# 09_USB.net
KiCad netlist of a schematic drawn in Altium Designer
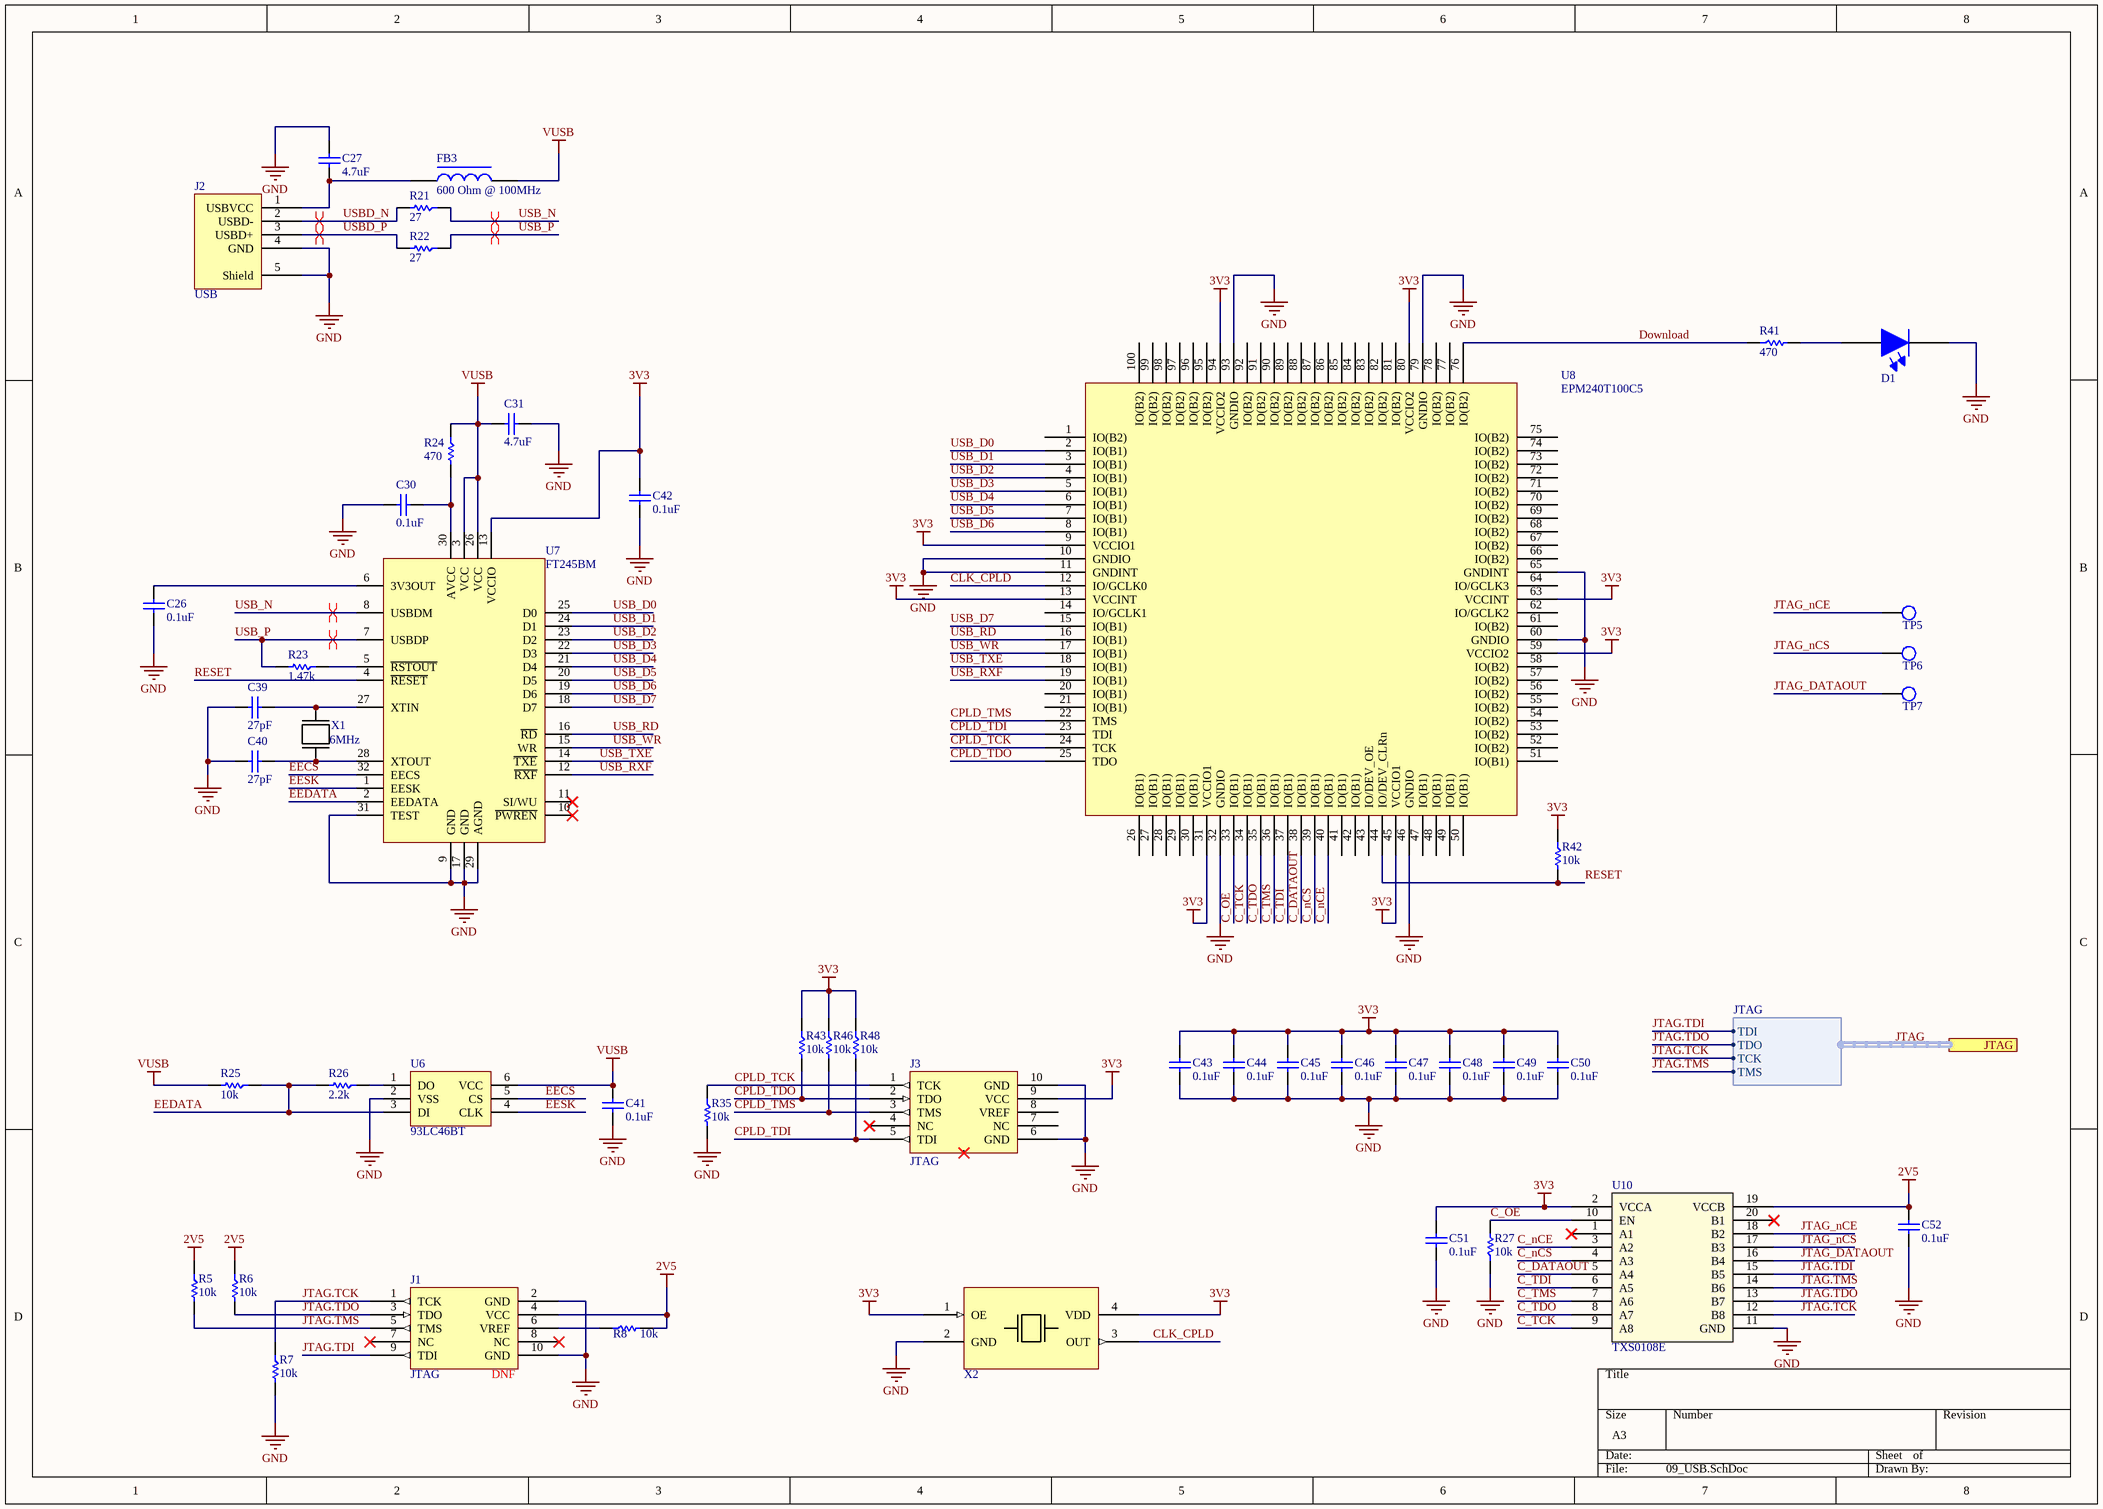
[diagram p0: 09_USB.SchDoc]

(export (version "E")
  (design (tool "Eeschema 10.0.6"))
  (components
    (comp (ref "C26")
      (value "0.1uF")
      (footprint "CAP0402R")
      (description "Capacitor")
      (libsource (lib "Quatro_SchLib") (part "C"))
    )
    (comp (ref "C27")
      (value "4.7uF")
      (footprint "CAP0805R")
      (description "Capacitor")
      (libsource (lib "Quatro_SchLib") (part "C"))
    )
    (comp (ref "C30")
      (value "0.1uF")
      (footprint "CAP0402R")
      (description "Capacitor")
      (libsource (lib "Quatro_SchLib") (part "C"))
    )
    (comp (ref "C31")
      (value "4.7uF")
      (footprint "CAP0805R")
      (description "Capacitor")
      (libsource (lib "Quatro_SchLib") (part "C"))
    )
    (comp (ref "C39")
      (value "27pF")
      (footprint "CAP0402R")
      (description "Capacitor")
      (libsource (lib "Quatro_SchLib") (part "C"))
    )
    (comp (ref "C40")
      (value "27pF")
      (footprint "CAP0402R")
      (description "Capacitor")
      (libsource (lib "Quatro_SchLib") (part "C"))
    )
    (comp (ref "C41")
      (value "0.1uF")
      (footprint "CAP0402R")
      (description "Capacitor")
      (libsource (lib "Quatro_SchLib") (part "C"))
    )
    (comp (ref "C42")
      (value "0.1uF")
      (footprint "CAP0402R")
      (description "Capacitor")
      (libsource (lib "Quatro_SchLib") (part "C"))
    )
    (comp (ref "C43")
      (value "0.1uF")
      (footprint "CAP0402R")
      (description "Capacitor")
      (libsource (lib "Quatro_SchLib") (part "C"))
    )
    (comp (ref "C44")
      (value "0.1uF")
      (footprint "CAP0402R")
      (description "Capacitor")
      (libsource (lib "Quatro_SchLib") (part "C"))
    )
    (comp (ref "C45")
      (value "0.1uF")
      (footprint "CAP0402R")
      (description "Capacitor")
      (libsource (lib "Quatro_SchLib") (part "C"))
    )
    (comp (ref "C46")
      (value "0.1uF")
      (footprint "CAP0402R")
      (description "Capacitor")
      (libsource (lib "Quatro_SchLib") (part "C"))
    )
    (comp (ref "C47")
      (value "0.1uF")
      (footprint "CAP0402R")
      (description "Capacitor")
      (libsource (lib "Quatro_SchLib") (part "C"))
    )
    (comp (ref "C48")
      (value "0.1uF")
      (footprint "CAP0402R")
      (description "Capacitor")
      (libsource (lib "Quatro_SchLib") (part "C"))
    )
    (comp (ref "C49")
      (value "0.1uF")
      (footprint "CAP0402R")
      (description "Capacitor")
      (libsource (lib "Quatro_SchLib") (part "C"))
    )
    (comp (ref "C50")
      (value "0.1uF")
      (footprint "CAP0402R")
      (description "Capacitor")
      (libsource (lib "Quatro_SchLib") (part "C"))
    )
    (comp (ref "C51")
      (value "0.1uF")
      (footprint "CAP0402R")
      (description "Capacitor")
      (libsource (lib "Quatro_SchLib") (part "C"))
    )
    (comp (ref "C52")
      (value "0.1uF")
      (footprint "CAP0402R")
      (description "Capacitor")
      (libsource (lib "Quatro_SchLib") (part "C"))
    )
    (comp (ref "D1")
      (value "LED")
      (footprint "0805D-RED")
      (description "Generic LED")
      (fields
        (field (name "01 CREATED BY") "Thomas Harper")
        (field (name "02 REVIEWED BY") "Rodrigo Maureira @ 2018-04-05")
        (field (name "PUBLISHER") "MUEEC")
      )
      (libsource (lib "Quatro_SchLib") (part "LED_SMD_Generic"))
    )
    (comp (ref "FB3")
      (value "600 Ohm @ 100MHz")
      (footprint "RES0805R")
      (description "Ferrite Bead")
      (libsource (lib "Quatro_SchLib") (part "Ferrite_Bead"))
    )
    (comp (ref "J1")
      (value "JTAG")
      (footprint "BOXEDVERT10")
      (description "JTAG connector")
      (fields (field (name "LOAD") "DNF"))
      (libsource (lib "Quatro_SchLib") (part "JTAG_CON"))
    )
    (comp (ref "J2")
      (value "USB")
      (footprint "USBPLUG")
      (description "USB B Type Connector")
      (libsource (lib "Quatro_SchLib") (part "USBPLUG"))
    )
    (comp (ref "J3")
      (value "JTAG")
      (footprint "TC2050-IDC-NL")
      (description "Contacts for TC2050-IDC-NL")
      (fields (field (name "01 CREATED BY") "Rodrigo Maureira") (field (name "PUBLISHER") "MUEEC"))
      (libsource (lib "Quatro_SchLib") (part "JTAG_CON_POGO"))
    )
    (comp (ref "R5")
      (value "10k")
      (footprint "RES0603R")
      (description "Resistor")
      (libsource (lib "Quatro_SchLib") (part "R"))
    )
    (comp (ref "R6")
      (value "10k")
      (footprint "RES0603R")
      (description "Resistor")
      (libsource (lib "Quatro_SchLib") (part "R"))
    )
    (comp (ref "R7")
      (value "10k")
      (footprint "RES0603R")
      (description "Resistor")
      (libsource (lib "Quatro_SchLib") (part "R"))
    )
    (comp (ref "R8")
      (value "10k")
      (footprint "RES0603R")
      (description "Resistor")
      (libsource (lib "Quatro_SchLib") (part "R"))
    )
    (comp (ref "R21")
      (value "27")
      (footprint "RES0402R")
      (description "Resistor")
      (libsource (lib "Quatro_SchLib") (part "R"))
    )
    (comp (ref "R22")
      (value "27")
      (footprint "RES0402R")
      (description "Resistor")
      (libsource (lib "Quatro_SchLib") (part "R"))
    )
    (comp (ref "R23")
      (value "1.47k")
      (footprint "RES0402R")
      (description "Resistor")
      (libsource (lib "Quatro_SchLib") (part "R"))
    )
    (comp (ref "R24")
      (value "470")
      (footprint "RES0402R")
      (description "Resistor")
      (libsource (lib "Quatro_SchLib") (part "R"))
    )
    (comp (ref "R25")
      (value "10k")
      (footprint "RES0603R")
      (description "Resistor")
      (libsource (lib "Quatro_SchLib") (part "R"))
    )
    (comp (ref "R26")
      (value "2.2k")
      (footprint "RES0603R")
      (description "Resistor")
      (libsource (lib "Quatro_SchLib") (part "R"))
    )
    (comp (ref "R27")
      (value "10k")
      (footprint "RES0603R")
      (description "Resistor")
      (libsource (lib "Quatro_SchLib") (part "R"))
    )
    (comp (ref "R35")
      (value "10k")
      (footprint "RES0603R")
      (description "Resistor")
      (libsource (lib "Quatro_SchLib") (part "R"))
    )
    (comp (ref "R41")
      (value "470")
      (footprint "RES0402R")
      (description "Resistor")
      (libsource (lib "Quatro_SchLib") (part "R"))
    )
    (comp (ref "R42")
      (value "10k")
      (footprint "RES0603R")
      (description "Resistor")
      (libsource (lib "Quatro_SchLib") (part "R"))
    )
    (comp (ref "R43")
      (value "10k")
      (footprint "RES0603R")
      (description "Resistor")
      (libsource (lib "Quatro_SchLib") (part "R"))
    )
    (comp (ref "R46")
      (value "10k")
      (footprint "RES0603R")
      (description "Resistor")
      (libsource (lib "Quatro_SchLib") (part "R"))
    )
    (comp (ref "R48")
      (value "10k")
      (footprint "RES0603R")
      (description "Resistor")
      (libsource (lib "Quatro_SchLib") (part "R"))
    )
    (comp (ref "TP5")
      (value "TestPoint")
      (footprint "TestPoint")
      (description "Test Point")
      (libsource (lib "Quatro_SchLib") (part "TestPoint"))
    )
    (comp (ref "TP6")
      (value "TestPoint")
      (footprint "TestPoint")
      (description "Test Point")
      (libsource (lib "Quatro_SchLib") (part "TestPoint"))
    )
    (comp (ref "TP7")
      (value "TestPoint")
      (footprint "TestPoint")
      (description "Test Point")
      (libsource (lib "Quatro_SchLib") (part "TestPoint"))
    )
    (comp (ref "U6")
      (value "93LC46BT")
      (footprint "SOT23-6")
      (description "1024-Bit Serial CMOS EEPROM")
      (libsource (lib "Quatro_SchLib") (part "FM93C46"))
    )
    (comp (ref "U7")
      (value "FT245BM")
      (footprint "LQFP32")
      (description "USB FIFO IC")
      (libsource (lib "Quatro_SchLib") (part "FT245BM"))
    )
    (comp (ref "U8")
      (value "EPM240T100C5")
      (footprint "TQFP100-14mm")
      (libsource (lib "Quatro_SchLib") (part "EPM240T100C5"))
    )
    (comp (ref "U10")
      (value "TXS0108E")
      (footprint "TSSOP20-4.4mm")
      (description "8-BIT BIDIRECTIONAL VOLTAGE-LEVEL TRANSLATOR  FOR OPEN-DRAIN AND PUSH-PULL APPLICATIONS")
      (libsource (lib "Quatro_SchLib") (part "TXS0108E"))
    )
    (comp (ref "X1")
      (value "6MHz")
      (footprint "HC-49/US")
      (description "ECS-60-20-5PX-TR")
      (libsource (lib "Quatro_SchLib") (part "Crystal 6MHz"))
    )
    (comp (ref "X2")
      (value "24Mhz Oscillator")
      (footprint "CX32225SB")
      (fields (field (name "01 CREATED BY") "Rodrigo Maureira") (field (name "PUBLISHER") "MUEEC"))
      (libsource (lib "Quatro_SchLib") (part "24Mhz Oscillator"))
    )
  )
  (nets
    (net (code "2") (name "/CLK_CPLD") (class "Default")
      (node (ref "U8") (pin "12") (pinfunction "IO/GCLK0_12") (pintype "passive"))
      (node (ref "X2") (pin "3") (pinfunction "OUT_3") (pintype "output"))
    )
    (net (code "3") (name "/CPLD_TCK") (class "Default")
      (node (ref "J3") (pin "1") (pinfunction "TCK_1") (pintype "output"))
      (node (ref "R35") (pin "1") (pintype "passive"))
      (node (ref "U8") (pin "24") (pinfunction "TCK_24") (pintype "passive"))
    )
    (net (code "4") (name "/CPLD_TDI") (class "Default")
      (node (ref "J3") (pin "5") (pinfunction "TDI_5") (pintype "output"))
      (node (ref "R48") (pin "2") (pintype "passive"))
      (node (ref "U8") (pin "23") (pinfunction "TDI_23") (pintype "passive"))
    )
    (net (code "5") (name "/CPLD_TDO") (class "Default")
      (node (ref "J3") (pin "2") (pinfunction "TDO_2") (pintype "input"))
      (node (ref "R43") (pin "2") (pintype "passive"))
      (node (ref "U8") (pin "25") (pinfunction "TDO_25") (pintype "passive"))
    )
    (net (code "6") (name "/CPLD_TMS") (class "Default")
      (node (ref "J3") (pin "3") (pinfunction "TMS_3") (pintype "output"))
      (node (ref "R46") (pin "2") (pintype "passive"))
      (node (ref "U8") (pin "22") (pinfunction "TMS_22") (pintype "passive"))
    )
    (net (code "7") (name "/C_DATAOUT") (class "Default")
      (node (ref "U10") (pin "5") (pinfunction "A4_5") (pintype "passive"))
      (node (ref "U8") (pin "38") (pinfunction "IO(B1)_38") (pintype "passive"))
    )
    (net (code "8") (name "/C_OE") (class "Default")
      (node (ref "R27") (pin "2") (pintype "passive"))
      (node (ref "U10") (pin "10") (pinfunction "EN_10") (pintype "passive"))
      (node (ref "U8") (pin "33") (pinfunction "IO(B1)_33") (pintype "passive"))
    )
    (net (code "9") (name "/C_TCK") (class "Default")
      (node (ref "U10") (pin "9") (pinfunction "A8_9") (pintype "passive"))
      (node (ref "U8") (pin "34") (pinfunction "IO(B1)_34") (pintype "passive"))
    )
    (net (code "10") (name "/C_TDI") (class "Default")
      (node (ref "U10") (pin "6") (pinfunction "A5_6") (pintype "passive"))
      (node (ref "U8") (pin "37") (pinfunction "IO(B1)_37") (pintype "passive"))
    )
    (net (code "11") (name "/C_TDO") (class "Default")
      (node (ref "U10") (pin "8") (pinfunction "A7_8") (pintype "passive"))
      (node (ref "U8") (pin "35") (pinfunction "IO(B1)_35") (pintype "passive"))
    )
    (net (code "12") (name "/C_TMS") (class "Default")
      (node (ref "U10") (pin "7") (pinfunction "A6_7") (pintype "passive"))
      (node (ref "U8") (pin "36") (pinfunction "IO(B1)_36") (pintype "passive"))
    )
    (net (code "13") (name "/C_nCE") (class "Default")
      (node (ref "U10") (pin "3") (pinfunction "A2_3") (pintype "passive"))
      (node (ref "U8") (pin "40") (pinfunction "IO(B1)_40") (pintype "passive"))
    )
    (net (code "14") (name "/C_nCS") (class "Default")
      (node (ref "U10") (pin "4") (pinfunction "A3_4") (pintype "passive"))
      (node (ref "U8") (pin "39") (pinfunction "IO(B1)_39") (pintype "passive"))
    )
    (net (code "15") (name "/Download") (class "Default")
      (node (ref "R41") (pin "1") (pintype "passive"))
      (node (ref "U8") (pin "76") (pinfunction "IO(B2)_76") (pintype "passive"))
    )
    (net (code "16") (name "/EECS") (class "Default")
      (node (ref "U6") (pin "5") (pinfunction "CS_5") (pintype "passive"))
      (node (ref "U7") (pin "32") (pinfunction "EECS_32") (pintype "passive"))
    )
    (net (code "17") (name "/EEDATA") (class "Default")
      (node (ref "R25") (pin "1") (pintype "passive"))
      (node (ref "R26") (pin "2") (pintype "passive"))
      (node (ref "U6") (pin "3") (pinfunction "DI_3") (pintype "passive"))
      (node (ref "U7") (pin "2") (pinfunction "EEDATA_2") (pintype "passive"))
    )
    (net (code "18") (name "/EESK") (class "Default")
      (node (ref "U6") (pin "4") (pinfunction "CLK_4") (pintype "passive"))
      (node (ref "U7") (pin "1") (pinfunction "EESK_1") (pintype "passive"))
    )
    (net (code "19") (name "/JTAG.TCK") (class "Default")
      (node (ref "J1") (pin "1") (pinfunction "TCK_1") (pintype "output"))
      (node (ref "R7") (pin "1") (pintype "passive"))
      (node (ref "U10") (pin "12") (pinfunction "B8_12") (pintype "passive"))
    )
    (net (code "20") (name "/JTAG.TDI") (class "Default")
      (node (ref "J1") (pin "9") (pinfunction "TDI_9") (pintype "output"))
      (node (ref "U10") (pin "15") (pinfunction "B5_15") (pintype "passive"))
    )
    (net (code "21") (name "/JTAG.TDO") (class "Default")
      (node (ref "J1") (pin "3") (pinfunction "TDO_3") (pintype "input"))
      (node (ref "R6") (pin "2") (pintype "passive"))
      (node (ref "U10") (pin "13") (pinfunction "B7_13") (pintype "passive"))
    )
    (net (code "22") (name "/JTAG.TMS") (class "Default")
      (node (ref "J1") (pin "5") (pinfunction "TMS_5") (pintype "output"))
      (node (ref "R5") (pin "2") (pintype "passive"))
      (node (ref "U10") (pin "14") (pinfunction "B6_14") (pintype "passive"))
    )
    (net (code "23") (name "/JTAG_DATAOUT") (class "Default")
      (node (ref "TP7") (pin "0") (pinfunction "TP_0") (pintype "passive"))
      (node (ref "U10") (pin "16") (pinfunction "B4_16") (pintype "passive"))
    )
    (net (code "24") (name "/JTAG_nCE") (class "Default")
      (node (ref "TP5") (pin "0") (pinfunction "TP_0") (pintype "passive"))
      (node (ref "U10") (pin "18") (pinfunction "B2_18") (pintype "passive"))
    )
    (net (code "25") (name "/JTAG_nCS") (class "Default")
      (node (ref "TP6") (pin "0") (pinfunction "TP_0") (pintype "passive"))
      (node (ref "U10") (pin "17") (pinfunction "B3_17") (pintype "passive"))
    )
    (net (code "27") (name "/RESET") (class "Default")
      (node (ref "R42") (pin "2") (pintype "passive"))
      (node (ref "U7") (pin "4") (pinfunction "~{RESET}_4") (pintype "passive"))
      (node (ref "U8") (pin "44") (pinfunction "IO/DEV_CLRn_44") (pintype "passive"))
    )
    (net (code "28") (name "/USBD_N") (class "Default")
      (node (ref "J2") (pin "2") (pinfunction "USBD-_2") (pintype "passive"))
      (node (ref "R21") (pin "2") (pintype "passive"))
    )
    (net (code "29") (name "/USBD_P") (class "Default")
      (node (ref "J2") (pin "3") (pinfunction "USBD+_3") (pintype "passive"))
      (node (ref "R22") (pin "2") (pintype "passive"))
    )
    (net (code "30") (name "/USB_D0") (class "Default")
      (node (ref "U7") (pin "25") (pinfunction "D0_25") (pintype "passive"))
      (node (ref "U8") (pin "2") (pinfunction "IO(B1)_2") (pintype "passive"))
    )
    (net (code "31") (name "/USB_D1") (class "Default")
      (node (ref "U7") (pin "24") (pinfunction "D1_24") (pintype "passive"))
      (node (ref "U8") (pin "3") (pinfunction "IO(B1)_3") (pintype "passive"))
    )
    (net (code "32") (name "/USB_D2") (class "Default")
      (node (ref "U7") (pin "23") (pinfunction "D2_23") (pintype "passive"))
      (node (ref "U8") (pin "4") (pinfunction "IO(B1)_4") (pintype "passive"))
    )
    (net (code "33") (name "/USB_D3") (class "Default")
      (node (ref "U7") (pin "22") (pinfunction "D3_22") (pintype "passive"))
      (node (ref "U8") (pin "5") (pinfunction "IO(B1)_5") (pintype "passive"))
    )
    (net (code "34") (name "/USB_D4") (class "Default")
      (node (ref "U7") (pin "21") (pinfunction "D4_21") (pintype "passive"))
      (node (ref "U8") (pin "6") (pinfunction "IO(B1)_6") (pintype "passive"))
    )
    (net (code "35") (name "/USB_D5") (class "Default")
      (node (ref "U7") (pin "20") (pinfunction "D5_20") (pintype "passive"))
      (node (ref "U8") (pin "7") (pinfunction "IO(B1)_7") (pintype "passive"))
    )
    (net (code "36") (name "/USB_D6") (class "Default")
      (node (ref "U7") (pin "19") (pinfunction "D6_19") (pintype "passive"))
      (node (ref "U8") (pin "8") (pinfunction "IO(B1)_8") (pintype "passive"))
    )
    (net (code "37") (name "/USB_D7") (class "Default")
      (node (ref "U7") (pin "18") (pinfunction "D7_18") (pintype "passive"))
      (node (ref "U8") (pin "15") (pinfunction "IO(B1)_15") (pintype "passive"))
    )
    (net (code "38") (name "/USB_N") (class "Default")
      (node (ref "R21") (pin "1") (pintype "passive"))
      (node (ref "U7") (pin "8") (pinfunction "USBDM_8") (pintype "passive"))
    )
    (net (code "39") (name "/USB_P") (class "Default")
      (node (ref "R22") (pin "1") (pintype "passive"))
      (node (ref "R23") (pin "2") (pintype "passive"))
      (node (ref "U7") (pin "7") (pinfunction "USBDP_7") (pintype "passive"))
    )
    (net (code "40") (name "/USB_RD") (class "Default")
      (node (ref "U7") (pin "16") (pinfunction "~{RD}_16") (pintype "passive"))
      (node (ref "U8") (pin "16") (pinfunction "IO(B1)_16") (pintype "passive"))
    )
    (net (code "41") (name "/USB_RXF") (class "Default")
      (node (ref "U7") (pin "12") (pinfunction "~{RXF}_12") (pintype "passive"))
      (node (ref "U8") (pin "19") (pinfunction "IO(B1)_19") (pintype "passive"))
    )
    (net (code "42") (name "/USB_TXE") (class "Default")
      (node (ref "U7") (pin "14") (pinfunction "~{TXE}_14") (pintype "passive"))
      (node (ref "U8") (pin "18") (pinfunction "IO(B1)_18") (pintype "passive"))
    )
    (net (code "43") (name "/USB_WR") (class "Default")
      (node (ref "U7") (pin "15") (pinfunction "WR_15") (pintype "passive"))
      (node (ref "U8") (pin "17") (pinfunction "IO(B1)_17") (pintype "passive"))
    )
    (net (code "44") (name "2V5") (class "Default")
      (node (ref "C52") (pin "1") (pinfunction "1_1") (pintype "passive"))
      (node (ref "J1") (pin "4") (pinfunction "VCC_4") (pintype "power_in"))
      (node (ref "R5") (pin "1") (pintype "passive"))
      (node (ref "R6") (pin "1") (pintype "passive"))
      (node (ref "R8") (pin "2") (pintype "passive"))
      (node (ref "U10") (pin "19") (pinfunction "VCCB_19") (pintype "passive"))
    )
    (net (code "45") (name "3V3") (class "Default")
      (node (ref "C42") (pin "2") (pinfunction "2_2") (pintype "passive"))
      (node (ref "C43") (pin "1") (pinfunction "1_1") (pintype "passive"))
      (node (ref "C44") (pin "1") (pinfunction "1_1") (pintype "passive"))
      (node (ref "C45") (pin "1") (pinfunction "1_1") (pintype "passive"))
      (node (ref "C46") (pin "1") (pinfunction "1_1") (pintype "passive"))
      (node (ref "C47") (pin "1") (pinfunction "1_1") (pintype "passive"))
      (node (ref "C48") (pin "1") (pinfunction "1_1") (pintype "passive"))
      (node (ref "C49") (pin "1") (pinfunction "1_1") (pintype "passive"))
      (node (ref "C50") (pin "1") (pinfunction "1_1") (pintype "passive"))
      (node (ref "C51") (pin "1") (pinfunction "1_1") (pintype "passive"))
      (node (ref "J3") (pin "9") (pinfunction "VCC_9") (pintype "power_in"))
      (node (ref "R42") (pin "1") (pintype "passive"))
      (node (ref "R43") (pin "1") (pintype "passive"))
      (node (ref "R46") (pin "1") (pintype "passive"))
      (node (ref "R48") (pin "1") (pintype "passive"))
      (node (ref "U10") (pin "2") (pinfunction "VCCA_2") (pintype "passive"))
      (node (ref "U7") (pin "13") (pinfunction "VCCIO_13") (pintype "passive"))
      (node (ref "U8") (pin "13") (pinfunction "VCCINT_13") (pintype "passive"))
      (node (ref "U8") (pin "31") (pinfunction "VCCIO1_31") (pintype "passive"))
      (node (ref "U8") (pin "45") (pinfunction "VCCIO1_45") (pintype "passive"))
      (node (ref "U8") (pin "59") (pinfunction "VCCIO2_59") (pintype "passive"))
      (node (ref "U8") (pin "63") (pinfunction "VCCINT_63") (pintype "passive"))
      (node (ref "U8") (pin "80") (pinfunction "VCCIO2_80") (pintype "passive"))
      (node (ref "U8") (pin "9") (pinfunction "VCCIO1_9") (pintype "passive"))
      (node (ref "U8") (pin "94") (pinfunction "VCCIO2_94") (pintype "passive"))
      (node (ref "X2") (pin "1") (pinfunction "OE_1") (pintype "input"))
      (node (ref "X2") (pin "4") (pinfunction "VDD_4") (pintype "power_in"))
    )
    (net (code "46") (name "GND") (class "Default")
      (node (ref "C26") (pin "2") (pinfunction "2_2") (pintype "passive"))
      (node (ref "C27") (pin "1") (pinfunction "1_1") (pintype "passive"))
      (node (ref "C30") (pin "1") (pinfunction "1_1") (pintype "passive"))
      (node (ref "C31") (pin "2") (pinfunction "2_2") (pintype "passive"))
      (node (ref "C39") (pin "1") (pinfunction "1_1") (pintype "passive"))
      (node (ref "C40") (pin "1") (pinfunction "1_1") (pintype "passive"))
      (node (ref "C41") (pin "1") (pinfunction "1_1") (pintype "passive"))
      (node (ref "C42") (pin "1") (pinfunction "1_1") (pintype "passive"))
      (node (ref "C43") (pin "2") (pinfunction "2_2") (pintype "passive"))
      (node (ref "C44") (pin "2") (pinfunction "2_2") (pintype "passive"))
      (node (ref "C45") (pin "2") (pinfunction "2_2") (pintype "passive"))
      (node (ref "C46") (pin "2") (pinfunction "2_2") (pintype "passive"))
      (node (ref "C47") (pin "2") (pinfunction "2_2") (pintype "passive"))
      (node (ref "C48") (pin "2") (pinfunction "2_2") (pintype "passive"))
      (node (ref "C49") (pin "2") (pinfunction "2_2") (pintype "passive"))
      (node (ref "C50") (pin "2") (pinfunction "2_2") (pintype "passive"))
      (node (ref "C51") (pin "2") (pinfunction "2_2") (pintype "passive"))
      (node (ref "C52") (pin "2") (pinfunction "2_2") (pintype "passive"))
      (node (ref "D1") (pin "K") (pinfunction "CATHODE_K") (pintype "passive"))
      (node (ref "J1") (pin "10") (pinfunction "GND_10") (pintype "passive"))
      (node (ref "J1") (pin "2") (pinfunction "GND_2") (pintype "passive"))
      (node (ref "J2") (pin "4") (pinfunction "GND_4") (pintype "passive"))
      (node (ref "J2") (pin "5") (pinfunction "Shield_5") (pintype "passive"))
      (node (ref "J3") (pin "10") (pinfunction "GND_10") (pintype "passive"))
      (node (ref "J3") (pin "6") (pinfunction "GND_6") (pintype "passive"))
      (node (ref "R27") (pin "1") (pintype "passive"))
      (node (ref "R35") (pin "2") (pintype "passive"))
      (node (ref "R7") (pin "2") (pintype "passive"))
      (node (ref "U10") (pin "11") (pinfunction "GND_11") (pintype "passive"))
      (node (ref "U6") (pin "2") (pinfunction "VSS_2") (pintype "passive"))
      (node (ref "U7") (pin "17") (pinfunction "GND_17") (pintype "passive"))
      (node (ref "U7") (pin "29") (pinfunction "AGND_29") (pintype "passive"))
      (node (ref "U7") (pin "31") (pinfunction "TEST_31") (pintype "passive"))
      (node (ref "U7") (pin "9") (pinfunction "GND_9") (pintype "passive"))
      (node (ref "U8") (pin "10") (pinfunction "GNDIO_10") (pintype "passive"))
      (node (ref "U8") (pin "11") (pinfunction "GNDINT_11") (pintype "passive"))
      (node (ref "U8") (pin "32") (pinfunction "GNDIO_32") (pintype "passive"))
      (node (ref "U8") (pin "46") (pinfunction "GNDIO_46") (pintype "passive"))
      (node (ref "U8") (pin "60") (pinfunction "GNDIO_60") (pintype "passive"))
      (node (ref "U8") (pin "65") (pinfunction "GNDINT_65") (pintype "passive"))
      (node (ref "U8") (pin "79") (pinfunction "GNDIO_79") (pintype "passive"))
      (node (ref "U8") (pin "93") (pinfunction "GNDIO_93") (pintype "passive"))
      (node (ref "X2") (pin "2") (pinfunction "GND_2") (pintype "power_in"))
    )
    (net (code "47") (name "Net-(D1-ANODE)") (class "Default")
      (node (ref "D1") (pin "A") (pinfunction "ANODE_A") (pintype "passive"))
      (node (ref "R41") (pin "2") (pintype "passive"))
    )
    (net (code "48") (name "Net-(J1-VREF)") (class "Default")
      (node (ref "J1") (pin "6") (pinfunction "VREF_6") (pintype "passive"))
      (node (ref "R8") (pin "1") (pintype "passive"))
    )
    (net (code "49") (name "Net-(J2-USBVCC)") (class "Default")
      (node (ref "C27") (pin "2") (pinfunction "2_2") (pintype "passive"))
      (node (ref "FB3") (pin "1") (pinfunction "1_1") (pintype "passive"))
      (node (ref "J2") (pin "1") (pinfunction "USBVCC_1") (pintype "passive"))
    )
    (net (code "50") (name "Net-(U6-DO)") (class "Default")
      (node (ref "R26") (pin "1") (pintype "passive"))
      (node (ref "U6") (pin "1") (pinfunction "DO_1") (pintype "passive"))
    )
    (net (code "51") (name "Net-(U7-3V3OUT)") (class "Default")
      (node (ref "C26") (pin "1") (pinfunction "1_1") (pintype "passive"))
      (node (ref "U7") (pin "6") (pinfunction "3V3OUT_6") (pintype "passive"))
    )
    (net (code "52") (name "Net-(U7-AVCC)") (class "Default")
      (node (ref "C30") (pin "2") (pinfunction "2_2") (pintype "passive"))
      (node (ref "R24") (pin "2") (pintype "passive"))
      (node (ref "U7") (pin "30") (pinfunction "AVCC_30") (pintype "passive"))
    )
    (net (code "53") (name "Net-(U7-XTIN)") (class "Default")
      (node (ref "C39") (pin "2") (pinfunction "2_2") (pintype "passive"))
      (node (ref "U7") (pin "27") (pinfunction "XTIN_27") (pintype "passive"))
      (node (ref "X1") (pin "1") (pinfunction "1_1") (pintype "passive"))
    )
    (net (code "54") (name "Net-(U7-XTOUT)") (class "Default")
      (node (ref "C40") (pin "2") (pinfunction "2_2") (pintype "passive"))
      (node (ref "U7") (pin "28") (pinfunction "XTOUT_28") (pintype "passive"))
      (node (ref "X1") (pin "2") (pinfunction "2_2") (pintype "passive"))
    )
    (net (code "55") (name "Net-(U7-~{RSTOUT})") (class "Default")
      (node (ref "R23") (pin "1") (pintype "passive"))
      (node (ref "U7") (pin "5") (pinfunction "~{RSTOUT}_5") (pintype "passive"))
    )
    (net (code "56") (name "VUSB") (class "Default")
      (node (ref "C31") (pin "1") (pinfunction "1_1") (pintype "passive"))
      (node (ref "C41") (pin "2") (pinfunction "2_2") (pintype "passive"))
      (node (ref "FB3") (pin "2") (pinfunction "2_2") (pintype "passive"))
      (node (ref "R24") (pin "1") (pintype "passive"))
      (node (ref "R25") (pin "2") (pintype "passive"))
      (node (ref "U6") (pin "6") (pinfunction "VCC_6") (pintype "passive"))
      (node (ref "U7") (pin "26") (pinfunction "VCC_26") (pintype "passive"))
      (node (ref "U7") (pin "3") (pinfunction "VCC_3") (pintype "passive"))
    )
    (net (code "57") (name "unconnected-(J1-NC-Pad7)") (class "Default")
      (node (ref "J1") (pin "7") (pinfunction "NC_7") (pintype "passive+no_connect"))
    )
    (net (code "58") (name "unconnected-(J1-NC-Pad8)") (class "Default")
      (node (ref "J1") (pin "8") (pinfunction "NC_8") (pintype "passive+no_connect"))
    )
    (net (code "59") (name "unconnected-(J3-NC-Pad4)") (class "Default")
      (node (ref "J3") (pin "4") (pinfunction "NC_4") (pintype "passive+no_connect"))
    )
    (net (code "60") (name "unconnected-(J3-NC-Pad7)") (class "Default")
      (node (ref "J3") (pin "7") (pinfunction "NC_7") (pintype "passive"))
    )
    (net (code "61") (name "unconnected-(J3-Pad0)") (class "Default")
      (node (ref "J3") (pin "0") (pinfunction "0_0") (pintype "passive+no_connect"))
    )
    (net (code "62") (name "unconnected-(J3-VREF-Pad8)") (class "Default")
      (node (ref "J3") (pin "8") (pinfunction "VREF_8") (pintype "passive"))
    )
    (net (code "63") (name "unconnected-(U7-SI{slash}WU-Pad11)") (class "Default")
      (node (ref "U7") (pin "11") (pinfunction "SI/WU_11") (pintype "passive+no_connect"))
    )
    (net (code "64") (name "unconnected-(U7-~{PWREN}-Pad10)") (class "Default")
      (node (ref "U7") (pin "10") (pinfunction "~{PWREN}_10") (pintype "passive+no_connect"))
    )
    (net (code "65") (name "unconnected-(U8-IO(B1)-Pad20)") (class "Default")
      (node (ref "U8") (pin "20") (pinfunction "IO(B1)_20") (pintype "passive"))
    )
    (net (code "66") (name "unconnected-(U8-IO(B1)-Pad21)") (class "Default")
      (node (ref "U8") (pin "21") (pinfunction "IO(B1)_21") (pintype "passive"))
    )
    (net (code "67") (name "unconnected-(U8-IO(B1)-Pad26)") (class "Default")
      (node (ref "U8") (pin "26") (pinfunction "IO(B1)_26") (pintype "passive"))
    )
    (net (code "68") (name "unconnected-(U8-IO(B1)-Pad27)") (class "Default")
      (node (ref "U8") (pin "27") (pinfunction "IO(B1)_27") (pintype "passive"))
    )
    (net (code "69") (name "unconnected-(U8-IO(B1)-Pad28)") (class "Default")
      (node (ref "U8") (pin "28") (pinfunction "IO(B1)_28") (pintype "passive"))
    )
    (net (code "70") (name "unconnected-(U8-IO(B1)-Pad29)") (class "Default")
      (node (ref "U8") (pin "29") (pinfunction "IO(B1)_29") (pintype "passive"))
    )
    (net (code "71") (name "unconnected-(U8-IO(B1)-Pad30)") (class "Default")
      (node (ref "U8") (pin "30") (pinfunction "IO(B1)_30") (pintype "passive"))
    )
    (net (code "72") (name "unconnected-(U8-IO(B1)-Pad41)") (class "Default")
      (node (ref "U8") (pin "41") (pinfunction "IO(B1)_41") (pintype "passive"))
    )
    (net (code "73") (name "unconnected-(U8-IO(B1)-Pad42)") (class "Default")
      (node (ref "U8") (pin "42") (pinfunction "IO(B1)_42") (pintype "passive"))
    )
    (net (code "74") (name "unconnected-(U8-IO(B1)-Pad47)") (class "Default")
      (node (ref "U8") (pin "47") (pinfunction "IO(B1)_47") (pintype "passive"))
    )
    (net (code "75") (name "unconnected-(U8-IO(B1)-Pad48)") (class "Default")
      (node (ref "U8") (pin "48") (pinfunction "IO(B1)_48") (pintype "passive"))
    )
    (net (code "76") (name "unconnected-(U8-IO(B1)-Pad49)") (class "Default")
      (node (ref "U8") (pin "49") (pinfunction "IO(B1)_49") (pintype "passive"))
    )
    (net (code "77") (name "unconnected-(U8-IO(B1)-Pad50)") (class "Default")
      (node (ref "U8") (pin "50") (pinfunction "IO(B1)_50") (pintype "passive"))
    )
    (net (code "78") (name "unconnected-(U8-IO(B1)-Pad51)") (class "Default")
      (node (ref "U8") (pin "51") (pinfunction "IO(B1)_51") (pintype "passive"))
    )
    (net (code "79") (name "unconnected-(U8-IO(B2)-Pad1)") (class "Default")
      (node (ref "U8") (pin "1") (pinfunction "IO(B2)_1") (pintype "passive"))
    )
    (net (code "80") (name "unconnected-(U8-IO(B2)-Pad52)") (class "Default")
      (node (ref "U8") (pin "52") (pinfunction "IO(B2)_52") (pintype "passive"))
    )
    (net (code "81") (name "unconnected-(U8-IO(B2)-Pad53)") (class "Default")
      (node (ref "U8") (pin "53") (pinfunction "IO(B2)_53") (pintype "passive"))
    )
    (net (code "82") (name "unconnected-(U8-IO(B2)-Pad54)") (class "Default")
      (node (ref "U8") (pin "54") (pinfunction "IO(B2)_54") (pintype "passive"))
    )
    (net (code "83") (name "unconnected-(U8-IO(B2)-Pad55)") (class "Default")
      (node (ref "U8") (pin "55") (pinfunction "IO(B2)_55") (pintype "passive"))
    )
    (net (code "84") (name "unconnected-(U8-IO(B2)-Pad56)") (class "Default")
      (node (ref "U8") (pin "56") (pinfunction "IO(B2)_56") (pintype "passive"))
    )
    (net (code "85") (name "unconnected-(U8-IO(B2)-Pad57)") (class "Default")
      (node (ref "U8") (pin "57") (pinfunction "IO(B2)_57") (pintype "passive"))
    )
    (net (code "86") (name "unconnected-(U8-IO(B2)-Pad58)") (class "Default")
      (node (ref "U8") (pin "58") (pinfunction "IO(B2)_58") (pintype "passive"))
    )
    (net (code "87") (name "unconnected-(U8-IO(B2)-Pad61)") (class "Default")
      (node (ref "U8") (pin "61") (pinfunction "IO(B2)_61") (pintype "passive"))
    )
    (net (code "88") (name "unconnected-(U8-IO(B2)-Pad66)") (class "Default")
      (node (ref "U8") (pin "66") (pinfunction "IO(B2)_66") (pintype "passive"))
    )
    (net (code "89") (name "unconnected-(U8-IO(B2)-Pad67)") (class "Default")
      (node (ref "U8") (pin "67") (pinfunction "IO(B2)_67") (pintype "passive"))
    )
    (net (code "90") (name "unconnected-(U8-IO(B2)-Pad68)") (class "Default")
      (node (ref "U8") (pin "68") (pinfunction "IO(B2)_68") (pintype "passive"))
    )
    (net (code "91") (name "unconnected-(U8-IO(B2)-Pad69)") (class "Default")
      (node (ref "U8") (pin "69") (pinfunction "IO(B2)_69") (pintype "passive"))
    )
    (net (code "92") (name "unconnected-(U8-IO(B2)-Pad70)") (class "Default")
      (node (ref "U8") (pin "70") (pinfunction "IO(B2)_70") (pintype "passive"))
    )
    (net (code "93") (name "unconnected-(U8-IO(B2)-Pad71)") (class "Default")
      (node (ref "U8") (pin "71") (pinfunction "IO(B2)_71") (pintype "passive"))
    )
    (net (code "94") (name "unconnected-(U8-IO(B2)-Pad72)") (class "Default")
      (node (ref "U8") (pin "72") (pinfunction "IO(B2)_72") (pintype "passive"))
    )
    (net (code "95") (name "unconnected-(U8-IO(B2)-Pad73)") (class "Default")
      (node (ref "U8") (pin "73") (pinfunction "IO(B2)_73") (pintype "passive"))
    )
    (net (code "96") (name "unconnected-(U8-IO(B2)-Pad74)") (class "Default")
      (node (ref "U8") (pin "74") (pinfunction "IO(B2)_74") (pintype "passive"))
    )
    (net (code "97") (name "unconnected-(U8-IO(B2)-Pad75)") (class "Default")
      (node (ref "U8") (pin "75") (pinfunction "IO(B2)_75") (pintype "passive"))
    )
    (net (code "98") (name "unconnected-(U8-IO(B2)-Pad77)") (class "Default")
      (node (ref "U8") (pin "77") (pinfunction "IO(B2)_77") (pintype "passive"))
    )
    (net (code "99") (name "unconnected-(U8-IO(B2)-Pad78)") (class "Default")
      (node (ref "U8") (pin "78") (pinfunction "IO(B2)_78") (pintype "passive"))
    )
    (net (code "100") (name "unconnected-(U8-IO(B2)-Pad81)") (class "Default")
      (node (ref "U8") (pin "81") (pinfunction "IO(B2)_81") (pintype "passive"))
    )
    (net (code "101") (name "unconnected-(U8-IO(B2)-Pad82)") (class "Default")
      (node (ref "U8") (pin "82") (pinfunction "IO(B2)_82") (pintype "passive"))
    )
    (net (code "102") (name "unconnected-(U8-IO(B2)-Pad83)") (class "Default")
      (node (ref "U8") (pin "83") (pinfunction "IO(B2)_83") (pintype "passive"))
    )
    (net (code "103") (name "unconnected-(U8-IO(B2)-Pad84)") (class "Default")
      (node (ref "U8") (pin "84") (pinfunction "IO(B2)_84") (pintype "passive"))
    )
    (net (code "104") (name "unconnected-(U8-IO(B2)-Pad85)") (class "Default")
      (node (ref "U8") (pin "85") (pinfunction "IO(B2)_85") (pintype "passive"))
    )
    (net (code "105") (name "unconnected-(U8-IO(B2)-Pad86)") (class "Default")
      (node (ref "U8") (pin "86") (pinfunction "IO(B2)_86") (pintype "passive"))
    )
    (net (code "106") (name "unconnected-(U8-IO(B2)-Pad87)") (class "Default")
      (node (ref "U8") (pin "87") (pinfunction "IO(B2)_87") (pintype "passive"))
    )
    (net (code "107") (name "unconnected-(U8-IO(B2)-Pad88)") (class "Default")
      (node (ref "U8") (pin "88") (pinfunction "IO(B2)_88") (pintype "passive"))
    )
    (net (code "108") (name "unconnected-(U8-IO(B2)-Pad89)") (class "Default")
      (node (ref "U8") (pin "89") (pinfunction "IO(B2)_89") (pintype "passive"))
    )
    (net (code "109") (name "unconnected-(U8-IO(B2)-Pad90)") (class "Default")
      (node (ref "U8") (pin "90") (pinfunction "IO(B2)_90") (pintype "passive"))
    )
    (net (code "110") (name "unconnected-(U8-IO(B2)-Pad91)") (class "Default")
      (node (ref "U8") (pin "91") (pinfunction "IO(B2)_91") (pintype "passive"))
    )
    (net (code "111") (name "unconnected-(U8-IO(B2)-Pad92)") (class "Default")
      (node (ref "U8") (pin "92") (pinfunction "IO(B2)_92") (pintype "passive"))
    )
    (net (code "112") (name "unconnected-(U8-IO(B2)-Pad95)") (class "Default")
      (node (ref "U8") (pin "95") (pinfunction "IO(B2)_95") (pintype "passive"))
    )
    (net (code "113") (name "unconnected-(U8-IO(B2)-Pad96)") (class "Default")
      (node (ref "U8") (pin "96") (pinfunction "IO(B2)_96") (pintype "passive"))
    )
    (net (code "114") (name "unconnected-(U8-IO(B2)-Pad97)") (class "Default")
      (node (ref "U8") (pin "97") (pinfunction "IO(B2)_97") (pintype "passive"))
    )
    (net (code "115") (name "unconnected-(U8-IO(B2)-Pad98)") (class "Default")
      (node (ref "U8") (pin "98") (pinfunction "IO(B2)_98") (pintype "passive"))
    )
    (net (code "116") (name "unconnected-(U8-IO(B2)-Pad99)") (class "Default")
      (node (ref "U8") (pin "99") (pinfunction "IO(B2)_99") (pintype "passive"))
    )
    (net (code "117") (name "unconnected-(U8-IO(B2)-Pad100)") (class "Default")
      (node (ref "U8") (pin "100") (pinfunction "IO(B2)_100") (pintype "passive"))
    )
    (net (code "118") (name "unconnected-(U8-IO{slash}DEV_OE-Pad43)") (class "Default")
      (node (ref "U8") (pin "43") (pinfunction "IO/DEV_OE_43") (pintype "passive"))
    )
    (net (code "119") (name "unconnected-(U8-IO{slash}GCLK1-Pad14)") (class "Default")
      (node (ref "U8") (pin "14") (pinfunction "IO/GCLK1_14") (pintype "passive"))
    )
    (net (code "120") (name "unconnected-(U8-IO{slash}GCLK2-Pad62)") (class "Default")
      (node (ref "U8") (pin "62") (pinfunction "IO/GCLK2_62") (pintype "passive"))
    )
    (net (code "121") (name "unconnected-(U8-IO{slash}GCLK3-Pad64)") (class "Default")
      (node (ref "U8") (pin "64") (pinfunction "IO/GCLK3_64") (pintype "passive"))
    )
    (net (code "122") (name "unconnected-(U10-A1-Pad1)") (class "Default")
      (node (ref "U10") (pin "1") (pinfunction "A1_1") (pintype "passive+no_connect"))
    )
    (net (code "123") (name "unconnected-(U10-B1-Pad20)") (class "Default")
      (node (ref "U10") (pin "20") (pinfunction "B1_20") (pintype "passive+no_connect"))
    )
  )
)
